# poe-neopixel-controller-v2.net
KiCad netlist of a schematic drawn in EAGLE
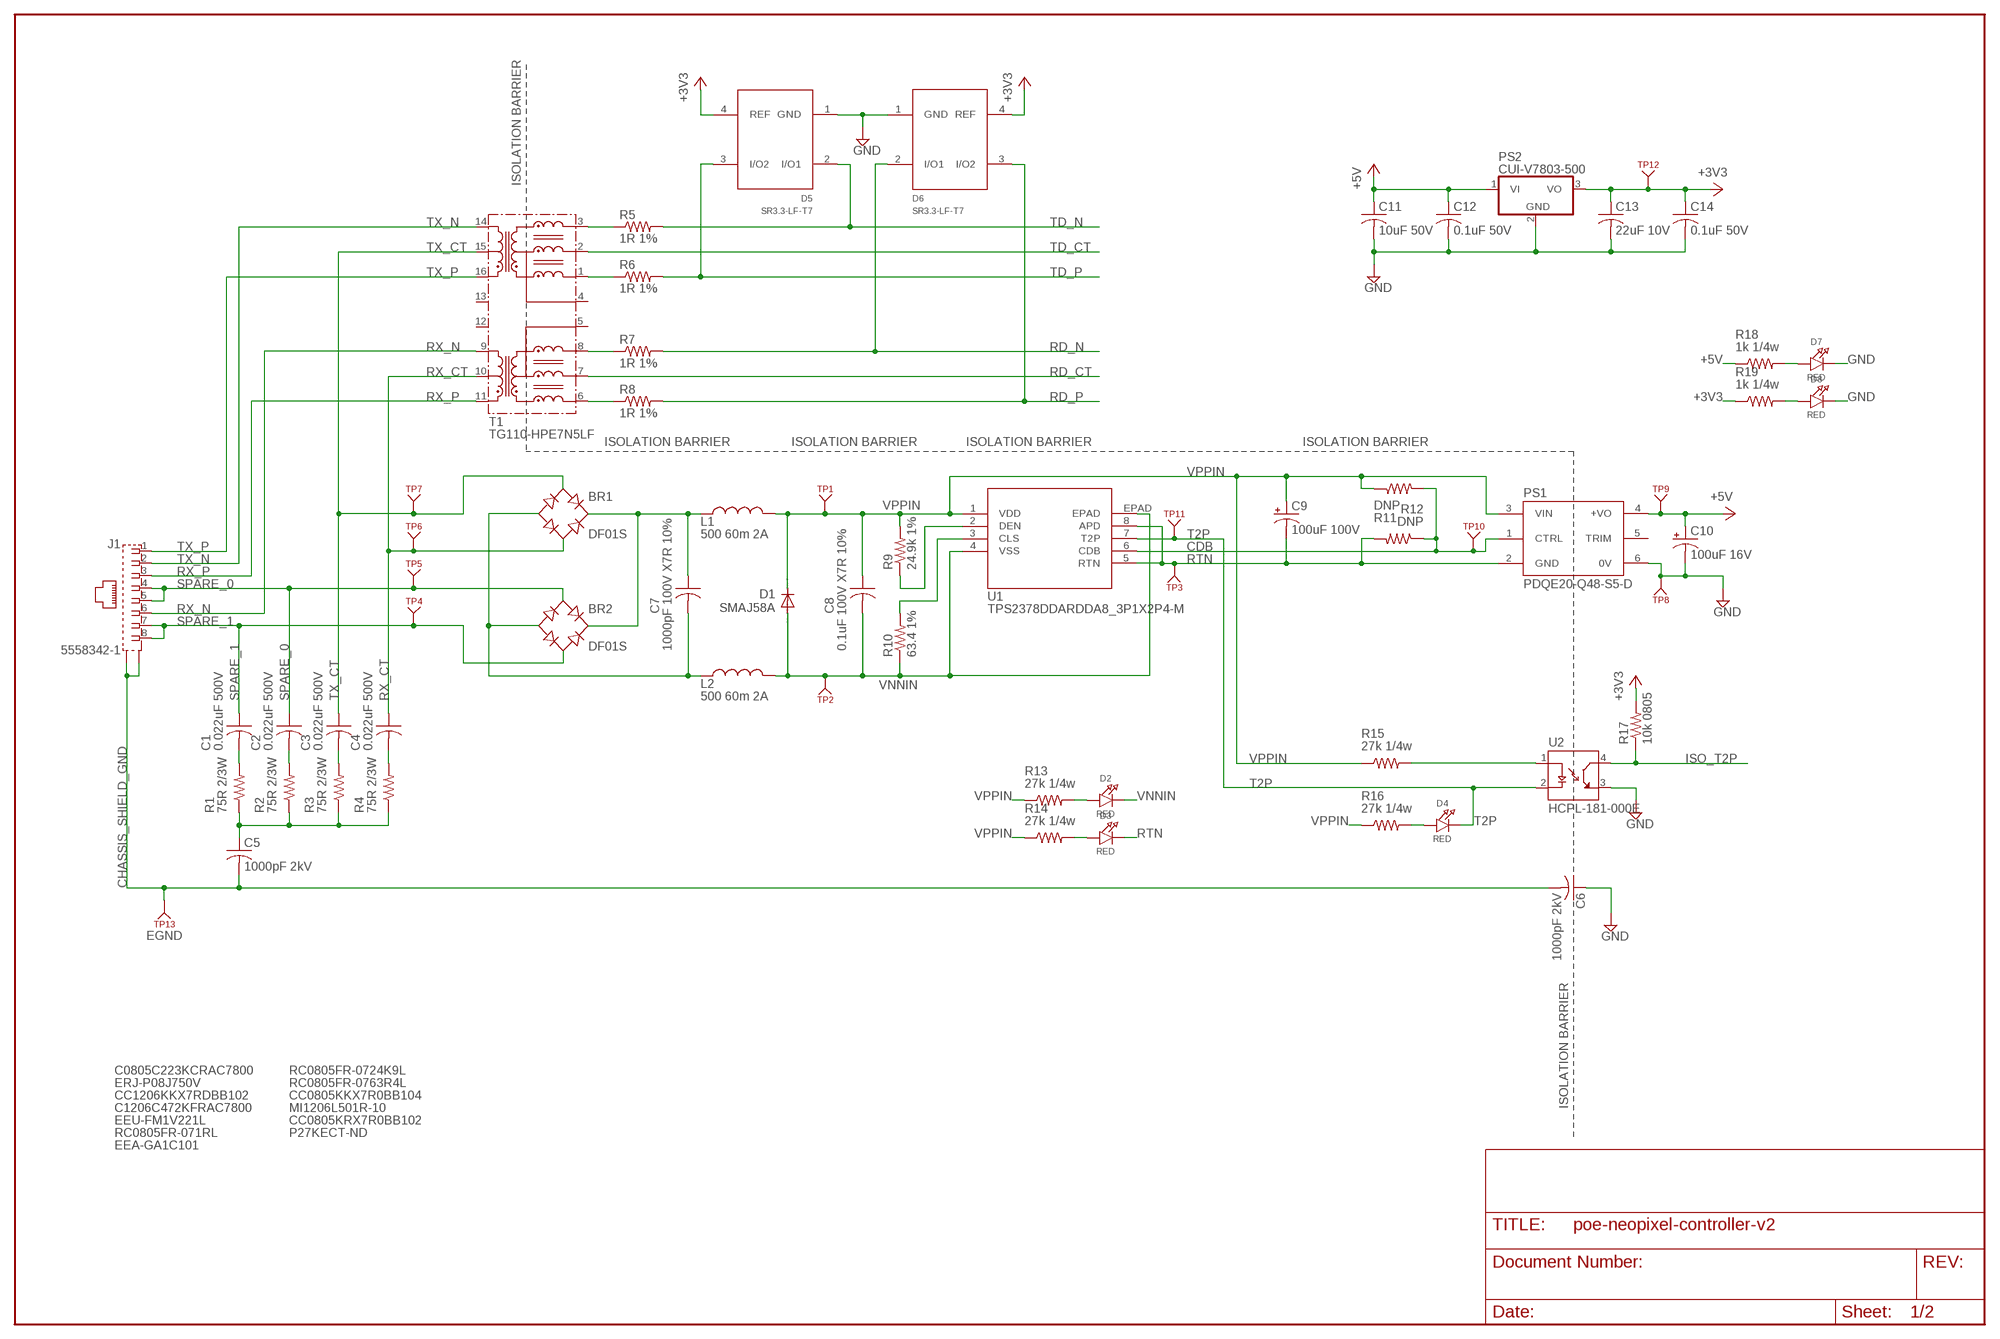
[diagram p0: schematic, sheet 1]
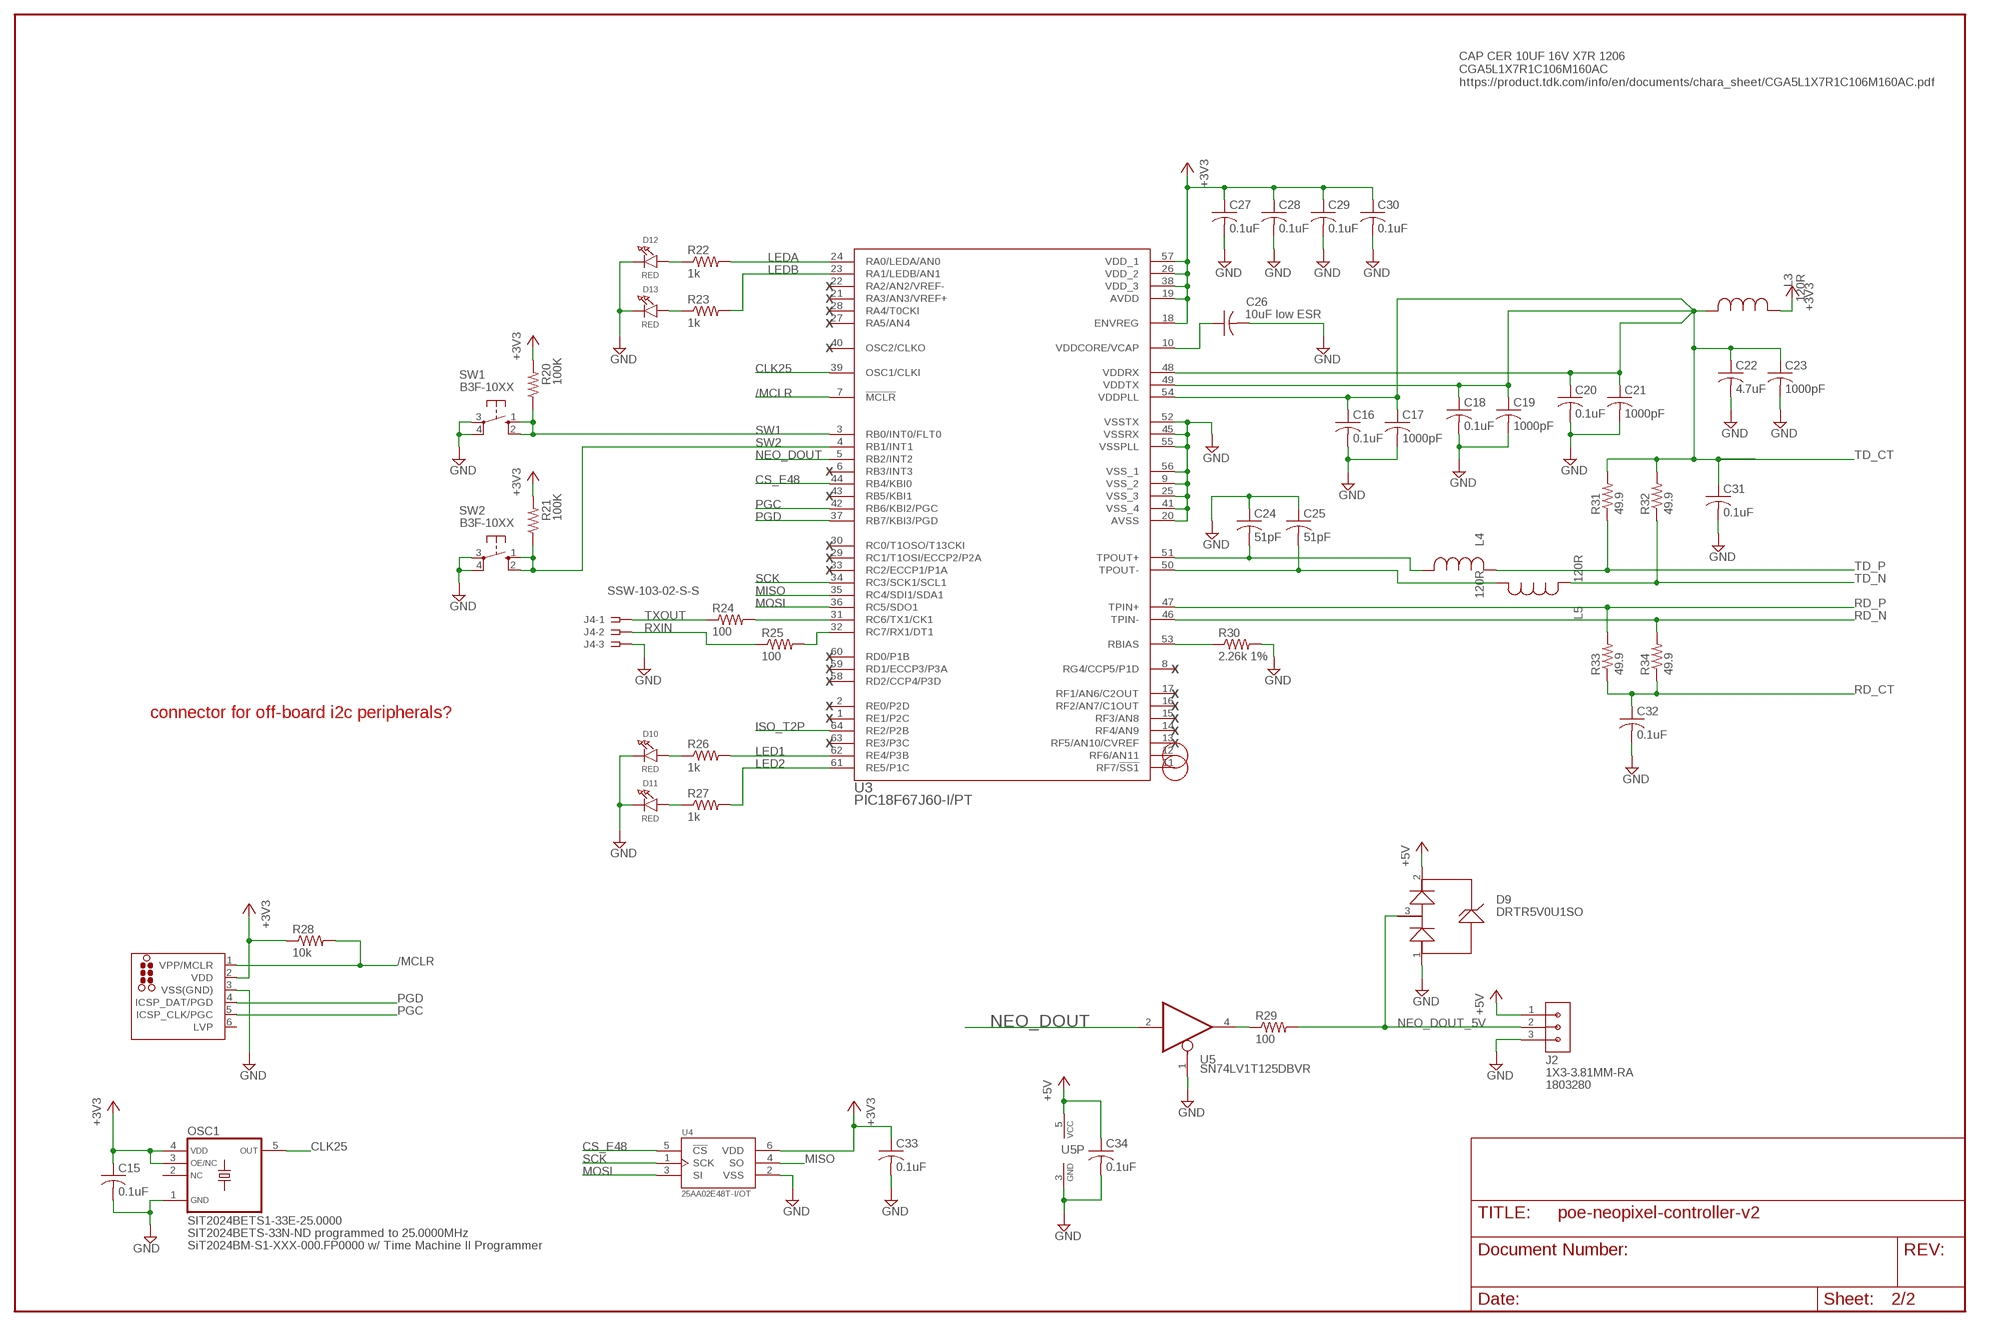
[diagram p1: schematic, sheet 2]

(export (version "E")
  (design (tool "Eeschema 10.0.6"))
  (components
    (comp (ref "C15")
      (value "0.1uF")
      (footprint "eagle-import:C0603")
      (libsource (lib "eagle-import") (part "C-USC0603"))
    )
    (comp (ref "C16")
      (value "0.1uF")
      (footprint "eagle-import:C0805")
      (libsource (lib "eagle-import") (part "C-USC0805"))
    )
    (comp (ref "C17")
      (value "1000pF")
      (footprint "eagle-import:C0805")
      (libsource (lib "eagle-import") (part "C-USC0805"))
    )
    (comp (ref "C18")
      (value "0.1uF")
      (footprint "eagle-import:C0805")
      (libsource (lib "eagle-import") (part "C-USC0805"))
    )
    (comp (ref "C19")
      (value "1000pF")
      (footprint "eagle-import:C0805")
      (libsource (lib "eagle-import") (part "C-USC0805"))
    )
    (comp (ref "C20")
      (value "0.1uF")
      (footprint "eagle-import:C0805")
      (libsource (lib "eagle-import") (part "C-USC0805"))
    )
    (comp (ref "C21")
      (value "1000pF")
      (footprint "eagle-import:C0805")
      (libsource (lib "eagle-import") (part "C-USC0805"))
    )
    (comp (ref "C22")
      (value "4.7uF")
      (footprint "eagle-import:C0805")
      (libsource (lib "eagle-import") (part "C-USC0805"))
    )
    (comp (ref "C23")
      (value "1000pF")
      (footprint "eagle-import:C0805")
      (libsource (lib "eagle-import") (part "C-USC0805"))
    )
    (comp (ref "C24")
      (value "51pF")
      (footprint "eagle-import:C0805")
      (libsource (lib "eagle-import") (part "C-USC0805"))
    )
    (comp (ref "C25")
      (value "51pF")
      (footprint "eagle-import:C0805")
      (libsource (lib "eagle-import") (part "C-USC0805"))
    )
    (comp (ref "C26")
      (value "10uF low ESR")
      (footprint "eagle-import:C1206")
      (libsource (lib "eagle-import") (part "resistor_C-USC1206"))
    )
    (comp (ref "C27")
      (value "0.1uF")
      (footprint "eagle-import:C0603")
      (libsource (lib "eagle-import") (part "C-USC0603"))
    )
    (comp (ref "C28")
      (value "0.1uF")
      (footprint "eagle-import:C0603")
      (libsource (lib "eagle-import") (part "C-USC0603"))
    )
    (comp (ref "C29")
      (value "0.1uF")
      (footprint "eagle-import:C0603")
      (libsource (lib "eagle-import") (part "C-USC0603"))
    )
    (comp (ref "C30")
      (value "0.1uF")
      (footprint "eagle-import:C0603")
      (libsource (lib "eagle-import") (part "C-USC0603"))
    )
    (comp (ref "C31")
      (value "0.1uF")
      (footprint "eagle-import:C0805")
      (libsource (lib "eagle-import") (part "C-USC0805"))
    )
    (comp (ref "C32")
      (value "0.1uF")
      (footprint "eagle-import:C0805")
      (libsource (lib "eagle-import") (part "C-USC0805"))
    )
    (comp (ref "C33")
      (value "0.1uF")
      (footprint "eagle-import:C0603")
      (libsource (lib "eagle-import") (part "C-USC0603"))
    )
    (comp (ref "C34")
      (value "0.1uF")
      (footprint "eagle-import:C0603")
      (libsource (lib "eagle-import") (part "C-USC0603"))
    )
    (comp (ref "D9")
      (value "DRTR5V0U1SO")
      (footprint "eagle-import:SOT23-3")
      (fields (field (name "MFR") "DIODES INC") (field (name "MFR_PART_NO") "DRTR5V0U1SO"))
      (libsource (lib "eagle-import") (part "DRTR5V0U1SO"))
    )
    (comp (ref "D10")
      (value "RED")
      (footprint "eagle-import:CHIPLED_0805_NOOUTLINE")
      (libsource (lib "eagle-import") (part "LED0805_NOOUTLINE"))
    )
    (comp (ref "D11")
      (value "RED")
      (footprint "eagle-import:CHIPLED_0805_NOOUTLINE")
      (libsource (lib "eagle-import") (part "LED0805_NOOUTLINE"))
    )
    (comp (ref "D12")
      (value "RED")
      (footprint "eagle-import:CHIPLED_0805_NOOUTLINE")
      (libsource (lib "eagle-import") (part "LED0805_NOOUTLINE"))
    )
    (comp (ref "D13")
      (value "RED")
      (footprint "eagle-import:CHIPLED_0805_NOOUTLINE")
      (libsource (lib "eagle-import") (part "LED0805_NOOUTLINE"))
    )
    (comp (ref "J2")
      (value "1X3-3.81MM-RA")
      (footprint "eagle-import:CON-PHOENIX-3.81-1X3-RA")
      (fields (field (name "MFR") "PHOENIX") (field (name "MFR_PART_NO") "1803280"))
      (libsource (lib "eagle-import") (part "CON-3.81MM-1X3-PHOENIX-RA"))
    )
    (comp (ref "J3")
      (value "TC2030-MCP-NL")
      (footprint "eagle-import:TC2030-MCP-NL")
      (libsource (lib "eagle-import") (part "TC2030-MCP-NL"))
    )
    (comp (ref "J4")
      (value "SSW-103-02-S-S")
      (footprint "eagle-import:SSW-103-02-S-S")
      (libsource (lib "eagle-import") (part "SSW-103-02-S-S"))
    )
    (comp (ref "L3")
      (value "120R")
      (footprint "eagle-import:IND_1608-M")
      (fields (field (name "MANUFACTURER_PART_NUMBER") "MMZ1608B121CTAH0"))
      (libsource (lib "eagle-import") (part "MMZ1608B121CTAH0IND_1608-M"))
    )
    (comp (ref "L4")
      (value "120R")
      (footprint "eagle-import:IND_1608-M")
      (fields (field (name "MANUFACTURER_PART_NUMBER") "MMZ1608B121CTAH0"))
      (libsource (lib "eagle-import") (part "MMZ1608B121CTAH0IND_1608-M"))
    )
    (comp (ref "L5")
      (value "120R")
      (footprint "eagle-import:IND_1608-M")
      (fields (field (name "MANUFACTURER_PART_NUMBER") "MMZ1608B121CTAH0"))
      (libsource (lib "eagle-import") (part "MMZ1608B121CTAH0IND_1608-M"))
    )
    (comp (ref "OSC1")
      (value "SIT2024BETS1-33E-25.0000")
      (footprint "eagle-import:SOT23-5")
      (libsource (lib "eagle-import") (part "SIT2024BETS1-33E-10.0000"))
    )
    (comp (ref "R20")
      (value "100K")
      (footprint "eagle-import:R0805")
      (libsource (lib "eagle-import") (part "R-US_R0805"))
    )
    (comp (ref "R21")
      (value "100K")
      (footprint "eagle-import:R0805")
      (libsource (lib "eagle-import") (part "R-US_R0805"))
    )
    (comp (ref "R22")
      (value "1k")
      (footprint "eagle-import:R0805")
      (libsource (lib "eagle-import") (part "R-US_R0805"))
    )
    (comp (ref "R23")
      (value "1k")
      (footprint "eagle-import:R0805")
      (libsource (lib "eagle-import") (part "R-US_R0805"))
    )
    (comp (ref "R24")
      (value "100")
      (footprint "eagle-import:R0805")
      (libsource (lib "eagle-import") (part "R-US_R0805"))
    )
    (comp (ref "R25")
      (value "100")
      (footprint "eagle-import:R0805")
      (libsource (lib "eagle-import") (part "R-US_R0805"))
    )
    (comp (ref "R26")
      (value "1k")
      (footprint "eagle-import:R0805")
      (libsource (lib "eagle-import") (part "R-US_R0805"))
    )
    (comp (ref "R27")
      (value "1k")
      (footprint "eagle-import:R0805")
      (libsource (lib "eagle-import") (part "R-US_R0805"))
    )
    (comp (ref "R28")
      (value "10k")
      (footprint "eagle-import:R0805")
      (libsource (lib "eagle-import") (part "R-US_R0805"))
    )
    (comp (ref "R29")
      (value "100")
      (footprint "eagle-import:R0805")
      (libsource (lib "eagle-import") (part "R-US_R0805"))
    )
    (comp (ref "R30")
      (value "2.26k 1%")
      (footprint "eagle-import:R0805")
      (libsource (lib "eagle-import") (part "R-US_R0805"))
    )
    (comp (ref "R31")
      (value "49.9")
      (footprint "eagle-import:R0805")
      (libsource (lib "eagle-import") (part "R-US_R0805"))
    )
    (comp (ref "R32")
      (value "49.9")
      (footprint "eagle-import:R0805")
      (libsource (lib "eagle-import") (part "R-US_R0805"))
    )
    (comp (ref "R33")
      (value "49.9")
      (footprint "eagle-import:R0805")
      (libsource (lib "eagle-import") (part "R-US_R0805"))
    )
    (comp (ref "R34")
      (value "49.9")
      (footprint "eagle-import:R0805")
      (libsource (lib "eagle-import") (part "R-US_R0805"))
    )
    (comp (ref "SW1")
      (value "B3F-10XX")
      (footprint "eagle-import:B3F-10XX")
      (libsource (lib "eagle-import") (part "10-XX"))
    )
    (comp (ref "SW2")
      (value "B3F-10XX")
      (footprint "eagle-import:B3F-10XX")
      (libsource (lib "eagle-import") (part "10-XX"))
    )
    (comp (ref "U3")
      (value "PIC18F67J60-I/PT")
      (footprint "eagle-import:TQFP64_10X10MC")
      (fields (field (name "MANUFACTURER_PART_NUMBER") "PIC18F67J60IPT"))
      (libsource (lib "eagle-import") (part "PIC18F67J60-I/PT"))
    )
    (comp (ref "U4")
      (value "25AA02E48T-I/OT")
      (footprint "eagle-import:SOT95P270X145-6N")
      (fields (field (name "DIGI-KEY_PART_NUMBER") "25AA02E48T-I/OTCT-ND") (field (name "MF") "Microchip"))
      (libsource (lib "eagle-import") (part "25AA02E48T-I/OT"))
    )
    (comp (ref "U5")
      (value "SN74LV1T125DBVR")
      (footprint "eagle-import:SOT23-5")
      (fields (field (name "MFR") "TI") (field (name "MFR_PART_NO") "SN74LV1T125DBVR"))
      (libsource (lib "eagle-import") (part "741G125DBVAHC"))
    )
    (comp (ref "BR1")
      (value "DF01S")
      (footprint "eagle-import:DFS")
      (libsource (lib "eagle-import") (part "DFS01"))
    )
    (comp (ref "BR2")
      (value "DF01S")
      (footprint "eagle-import:DFS")
      (libsource (lib "eagle-import") (part "DFS01"))
    )
    (comp (ref "C1")
      (value "0.022uF 500V")
      (footprint "eagle-import:C1206")
      (libsource (lib "eagle-import") (part "C-USC1206"))
    )
    (comp (ref "C2")
      (value "0.022uF 500V")
      (footprint "eagle-import:C1206")
      (libsource (lib "eagle-import") (part "C-USC1206"))
    )
    (comp (ref "C3")
      (value "0.022uF 500V")
      (footprint "eagle-import:C1206")
      (libsource (lib "eagle-import") (part "C-USC1206"))
    )
    (comp (ref "C4")
      (value "0.022uF 500V")
      (footprint "eagle-import:C1206")
      (libsource (lib "eagle-import") (part "C-USC1206"))
    )
    (comp (ref "C5")
      (value "1000pF 2kV")
      (footprint "eagle-import:C1206K")
      (libsource (lib "eagle-import") (part "C-USC1206K"))
    )
    (comp (ref "C6")
      (value "1000pF 2kV")
      (footprint "eagle-import:C1206K")
      (libsource (lib "eagle-import") (part "C-USC1206K"))
    )
    (comp (ref "C7")
      (value "1000pF 100V X7R 10%")
      (footprint "eagle-import:C0805")
      (libsource (lib "eagle-import") (part "C-USC0805"))
    )
    (comp (ref "C8")
      (value "0.1uF 100V X7R 10%")
      (footprint "eagle-import:C0805")
      (libsource (lib "eagle-import") (part "C-USC0805"))
    )
    (comp (ref "C9")
      (value "100uF 100V")
      (footprint "eagle-import:E5-10,5")
      (libsource (lib "eagle-import") (part "CPOL-USE5-10.5"))
    )
    (comp (ref "C10")
      (value "100uF 16V")
      (footprint "eagle-import:E2,5-7")
      (libsource (lib "eagle-import") (part "CPOL-USE2.5-7"))
    )
    (comp (ref "C11")
      (value "10uF 50V")
      (footprint "eagle-import:C1210K")
      (fields (field (name "MFR") "KEMET") (field (name "MFR_PART_NO") "C1210C106K5RACTU"))
      (libsource (lib "eagle-import") (part "C-USC1210K"))
    )
    (comp (ref "C12")
      (value "0.1uF 50V")
      (footprint "eagle-import:C0805")
      (fields (field (name "MFR") "KEMET") (field (name "MFR_PART_NO") "C1206S104M5RACTU"))
      (libsource (lib "eagle-import") (part "C-USC0805"))
    )
    (comp (ref "C13")
      (value "22uF 10V")
      (footprint "eagle-import:C1206K")
      (fields (field (name "MFR") "KEMET") (field (name "MFR_PART_NO") "C1206C226K8RAC7800"))
      (libsource (lib "eagle-import") (part "C-USC1206K"))
    )
    (comp (ref "C14")
      (value "0.1uF 50V")
      (footprint "eagle-import:C0805")
      (fields (field (name "MFR") "KEMET") (field (name "MFR_PART_NO") "C1206S104M5RACTU"))
      (libsource (lib "eagle-import") (part "C-USC0805"))
    )
    (comp (ref "D1")
      (value "SMAJ58A")
      (footprint "eagle-import:DO214AC")
      (libsource (lib "eagle-import") (part "DIODE-DO214AC"))
    )
    (comp (ref "D2")
      (value "RED")
      (footprint "eagle-import:CHIPLED_0805_NOOUTLINE")
      (libsource (lib "eagle-import") (part "LED0805_NOOUTLINE"))
    )
    (comp (ref "D3")
      (value "RED")
      (footprint "eagle-import:CHIPLED_0805_NOOUTLINE")
      (libsource (lib "eagle-import") (part "LED0805_NOOUTLINE"))
    )
    (comp (ref "D4")
      (value "RED")
      (footprint "eagle-import:CHIPLED_0805_NOOUTLINE")
      (libsource (lib "eagle-import") (part "LED0805_NOOUTLINE"))
    )
    (comp (ref "D5")
      (value "SR3.3-LF-T7")
      (footprint "eagle-import:SOT143B")
      (libsource (lib "eagle-import") (part "SR3.3-LF-T7"))
    )
    (comp (ref "D6")
      (value "SR3.3-LF-T7")
      (footprint "eagle-import:SOT143B")
      (libsource (lib "eagle-import") (part "SR3.3-LF-T7"))
    )
    (comp (ref "D7")
      (value "RED")
      (footprint "eagle-import:CHIPLED_0805_NOOUTLINE")
      (libsource (lib "eagle-import") (part "LED0805_NOOUTLINE"))
    )
    (comp (ref "D8")
      (value "RED")
      (footprint "eagle-import:CHIPLED_0805_NOOUTLINE")
      (libsource (lib "eagle-import") (part "LED0805_NOOUTLINE"))
    )
    (comp (ref "J1")
      (value "5558342-1")
      (footprint "eagle-import:TE_5558342-1")
      (fields (field (name "DIGI-KEY_PART_NUMBER") "A31466-ND") (field (name "MF") "TE Connectivity"))
      (libsource (lib "eagle-import") (part "5558342-1"))
    )
    (comp (ref "L1")
      (value "500 60m 2A")
      (footprint "eagle-import:L3216C")
      (libsource (lib "eagle-import") (part "L-USL3216C"))
    )
    (comp (ref "L2")
      (value "500 60m 2A")
      (footprint "eagle-import:L3216C")
      (libsource (lib "eagle-import") (part "L-USL3216C"))
    )
    (comp (ref "PS1")
      (value "PDQE20-Q48-S5-D")
      (footprint "eagle-import:CONV_PDQE20-Q48-S5-D")
      (fields (field (name "DIGI-KEY_PART_NUMBER") "102-6272-ND") (field (name "MF") "CUI Inc."))
      (libsource (lib "eagle-import") (part "PDQE20-Q48-S5-D"))
    )
    (comp (ref "PS2")
      (value "CUI-V7803-500")
      (footprint "eagle-import:CUI-78XX-500")
      (libsource (lib "eagle-import") (part "CUI-V7803-500"))
    )
    (comp (ref "R1")
      (value "75R 2/3W")
      (footprint "eagle-import:R1206")
      (libsource (lib "eagle-import") (part "R-US_R1206"))
    )
    (comp (ref "R2")
      (value "75R 2/3W")
      (footprint "eagle-import:R1206")
      (libsource (lib "eagle-import") (part "R-US_R1206"))
    )
    (comp (ref "R3")
      (value "75R 2/3W")
      (footprint "eagle-import:R1206")
      (libsource (lib "eagle-import") (part "R-US_R1206"))
    )
    (comp (ref "R4")
      (value "75R 2/3W")
      (footprint "eagle-import:R1206")
      (libsource (lib "eagle-import") (part "R-US_R1206"))
    )
    (comp (ref "R5")
      (value "1R 1%")
      (footprint "eagle-import:R0805")
      (libsource (lib "eagle-import") (part "R-US_R0805"))
    )
    (comp (ref "R6")
      (value "1R 1%")
      (footprint "eagle-import:R0805")
      (libsource (lib "eagle-import") (part "R-US_R0805"))
    )
    (comp (ref "R7")
      (value "1R 1%")
      (footprint "eagle-import:R0805")
      (libsource (lib "eagle-import") (part "R-US_R0805"))
    )
    (comp (ref "R8")
      (value "1R 1%")
      (footprint "eagle-import:R0805")
      (libsource (lib "eagle-import") (part "R-US_R0805"))
    )
    (comp (ref "R9")
      (value "24.9k 1%")
      (footprint "eagle-import:R0805")
      (libsource (lib "eagle-import") (part "R-US_R0805"))
    )
    (comp (ref "R10")
      (value "63.4 1%")
      (footprint "eagle-import:R0805")
      (libsource (lib "eagle-import") (part "R-US_R0805"))
    )
    (comp (ref "R11")
      (value "DNP")
      (footprint "eagle-import:R1206")
      (libsource (lib "eagle-import") (part "R-US_R1206"))
    )
    (comp (ref "R12")
      (value "DNP")
      (footprint "eagle-import:R1206")
      (libsource (lib "eagle-import") (part "R-US_R1206"))
    )
    (comp (ref "R13")
      (value "27k 1/4w")
      (footprint "eagle-import:R1206")
      (libsource (lib "eagle-import") (part "R-US_R1206"))
    )
    (comp (ref "R14")
      (value "27k 1/4w")
      (footprint "eagle-import:R1206")
      (libsource (lib "eagle-import") (part "R-US_R1206"))
    )
    (comp (ref "R15")
      (value "27k 1/4w")
      (footprint "eagle-import:R1206")
      (libsource (lib "eagle-import") (part "R-US_R1206"))
    )
    (comp (ref "R16")
      (value "27k 1/4w")
      (footprint "eagle-import:R1206")
      (libsource (lib "eagle-import") (part "R-US_R1206"))
    )
    (comp (ref "R17")
      (value "10k 0805")
      (footprint "eagle-import:R0805")
      (libsource (lib "eagle-import") (part "resistor_R-US_R0805"))
    )
    (comp (ref "R18")
      (value "1k 1/4w")
      (footprint "eagle-import:R0805")
      (libsource (lib "eagle-import") (part "R-US_R0805"))
    )
    (comp (ref "R19")
      (value "1k 1/4w")
      (footprint "eagle-import:R0805")
      (libsource (lib "eagle-import") (part "R-US_R0805"))
    )
    (comp (ref "T1")
      (value "TG110-HPE7N5LF")
      (footprint "eagle-import:RP-ULTRA")
      (libsource (lib "eagle-import") (part "TG110-HPE7N5LF"))
    )
    (comp (ref "TP1")
      (value "KEYSTONE_500X")
      (footprint "eagle-import:KEYSTONE_TP500X")
      (libsource (lib "eagle-import") (part "KEYSTONE_500X"))
    )
    (comp (ref "TP2")
      (value "KEYSTONE_500X")
      (footprint "eagle-import:KEYSTONE_TP500X")
      (libsource (lib "eagle-import") (part "KEYSTONE_500X"))
    )
    (comp (ref "TP3")
      (value "KEYSTONE_500X")
      (footprint "eagle-import:KEYSTONE_TP500X")
      (libsource (lib "eagle-import") (part "KEYSTONE_500X"))
    )
    (comp (ref "TP4")
      (value "KEYSTONE_500X")
      (footprint "eagle-import:KEYSTONE_TP500X")
      (libsource (lib "eagle-import") (part "KEYSTONE_500X"))
    )
    (comp (ref "TP5")
      (value "KEYSTONE_500X")
      (footprint "eagle-import:KEYSTONE_TP500X")
      (libsource (lib "eagle-import") (part "KEYSTONE_500X"))
    )
    (comp (ref "TP6")
      (value "KEYSTONE_500X")
      (footprint "eagle-import:KEYSTONE_TP500X")
      (libsource (lib "eagle-import") (part "KEYSTONE_500X"))
    )
    (comp (ref "TP7")
      (value "KEYSTONE_500X")
      (footprint "eagle-import:KEYSTONE_TP500X")
      (libsource (lib "eagle-import") (part "KEYSTONE_500X"))
    )
    (comp (ref "TP8")
      (value "KEYSTONE_500X")
      (footprint "eagle-import:KEYSTONE_TP500X")
      (libsource (lib "eagle-import") (part "KEYSTONE_500X"))
    )
    (comp (ref "TP9")
      (value "KEYSTONE_500X")
      (footprint "eagle-import:KEYSTONE_TP500X")
      (libsource (lib "eagle-import") (part "KEYSTONE_500X"))
    )
    (comp (ref "TP10")
      (value "KEYSTONE_500X")
      (footprint "eagle-import:KEYSTONE_TP500X")
      (libsource (lib "eagle-import") (part "KEYSTONE_500X"))
    )
    (comp (ref "TP11")
      (value "KEYSTONE_500X")
      (footprint "eagle-import:KEYSTONE_TP500X")
      (libsource (lib "eagle-import") (part "KEYSTONE_500X"))
    )
    (comp (ref "TP12")
      (value "KEYSTONE_500X")
      (footprint "eagle-import:KEYSTONE_TP500X")
      (libsource (lib "eagle-import") (part "KEYSTONE_500X"))
    )
    (comp (ref "TP13")
      (value "KEYSTONE_500X")
      (footprint "eagle-import:KEYSTONE_TP500X")
      (libsource (lib "eagle-import") (part "KEYSTONE_500X"))
    )
    (comp (ref "U1")
      (value "TPS2378DDARDDA8_3P1X2P4-M")
      (footprint "eagle-import:DDA8_3P1X2P4-M")
      (fields (field (name "MANUFACTURER_PART_NUMBER") "TPS2378DDAR"))
      (libsource (lib "eagle-import") (part "TPS2378DDARDDA8_3P1X2P4-M"))
    )
    (comp (ref "U2")
      (value "HCPL-181-000E")
      (footprint "eagle-import:SOIC254P675X240-4N")
      (fields (field (name "DIGI-KEY_PART_NUMBER") "516-1646-1-ND") (field (name "MF") "Broadcom Limited"))
      (libsource (lib "eagle-import") (part "HCPL-181-000E"))
    )
  )
  (nets
    (net (code "1") (name "+3V3") (class "Default")
      (node (ref "C13") (pin "1") (pinfunction "1_1") (pintype "passive"))
      (node (ref "C14") (pin "1") (pinfunction "1_1") (pintype "passive"))
      (node (ref "C15") (pin "1") (pinfunction "1_1") (pintype "passive"))
      (node (ref "C27") (pin "1") (pinfunction "1_1") (pintype "passive"))
      (node (ref "C28") (pin "1") (pinfunction "1_1") (pintype "passive"))
      (node (ref "C29") (pin "1") (pinfunction "1_1") (pintype "passive"))
      (node (ref "C30") (pin "1") (pinfunction "1_1") (pintype "passive"))
      (node (ref "C33") (pin "1") (pinfunction "1_1") (pintype "passive"))
      (node (ref "D5") (pin "4") (pinfunction "REF_4") (pintype "bidirectional"))
      (node (ref "D6") (pin "4") (pinfunction "REF_4") (pintype "bidirectional"))
      (node (ref "J3") (pin "2") (pinfunction "VDD_2") (pintype "power_in"))
      (node (ref "L3") (pin "2") (pinfunction "2_2") (pintype "passive"))
      (node (ref "OSC1") (pin "3") (pinfunction "OE/NC_3") (pintype "bidirectional"))
      (node (ref "OSC1") (pin "4") (pinfunction "VDD_4") (pintype "bidirectional"))
      (node (ref "PS2") (pin "3") (pinfunction "VO_3") (pintype "passive"))
      (node (ref "R17") (pin "2") (pinfunction "2_2") (pintype "passive"))
      (node (ref "R19") (pin "1") (pinfunction "1_1") (pintype "passive"))
      (node (ref "R20") (pin "2") (pinfunction "2_2") (pintype "passive"))
      (node (ref "R21") (pin "2") (pinfunction "2_2") (pintype "passive"))
      (node (ref "R28") (pin "1") (pinfunction "1_1") (pintype "passive"))
      (node (ref "TP12") (pin "1") (pinfunction "P$1_1") (pintype "bidirectional"))
      (node (ref "U3") (pin "18") (pinfunction "ENVREG_18") (pintype "passive"))
      (node (ref "U3") (pin "19") (pinfunction "AVDD_19") (pintype "passive"))
      (node (ref "U3") (pin "26") (pinfunction "VDD_2_26") (pintype "passive"))
      (node (ref "U3") (pin "38") (pinfunction "VDD_3_38") (pintype "passive"))
      (node (ref "U3") (pin "57") (pinfunction "VDD_1_57") (pintype "passive"))
      (node (ref "U4") (pin "6") (pinfunction "VDD_6") (pintype "power_in"))
    )
    (net (code "2") (name "+5V") (class "Default")
      (node (ref "C10") (pin "+") (pinfunction "+_+") (pintype "passive"))
      (node (ref "C11") (pin "1") (pinfunction "1_1") (pintype "passive"))
      (node (ref "C12") (pin "1") (pinfunction "1_1") (pintype "passive"))
      (node (ref "C34") (pin "1") (pinfunction "1_1") (pintype "passive"))
      (node (ref "D9") (pin "2") (pinfunction "2_2") (pintype "bidirectional"))
      (node (ref "J2") (pin "1") (pinfunction "1_1") (pintype "bidirectional"))
      (node (ref "PS1") (pin "4") (pinfunction "+VO_4") (pintype "output"))
      (node (ref "PS2") (pin "1") (pinfunction "VI_1") (pintype "input"))
      (node (ref "R18") (pin "1") (pinfunction "1_1") (pintype "passive"))
      (node (ref "TP9") (pin "1") (pinfunction "P$1_1") (pintype "bidirectional"))
      (node (ref "U5") (pin "5") (pinfunction "VCC_5") (pintype "power_in"))
    )
    (net (code "3") (name "CDB") (class "Default")
      (node (ref "PS1") (pin "1") (pinfunction "CTRL_1") (pintype "input"))
      (node (ref "R11") (pin "2") (pinfunction "2_2") (pintype "passive"))
      (node (ref "R12") (pin "1") (pinfunction "1_1") (pintype "passive"))
      (node (ref "TP10") (pin "1") (pinfunction "P$1_1") (pintype "bidirectional"))
      (node (ref "U1") (pin "6") (pinfunction "CDB_6") (pintype "output"))
    )
    (net (code "4") (name "CHASSIS_SHIELD_GND") (class "Default")
      (node (ref "C5") (pin "2") (pinfunction "2_2") (pintype "passive"))
      (node (ref "C6") (pin "2") (pinfunction "2_2") (pintype "passive"))
      (node (ref "J1") (pin "SH1") (pinfunction "S1_SH1") (pintype "passive"))
      (node (ref "J1") (pin "SH2") (pinfunction "S2_SH2") (pintype "passive"))
      (node (ref "TP13") (pin "1") (pinfunction "P$1_1") (pintype "bidirectional"))
    )
    (net (code "5") (name "CLK25") (class "Default")
      (node (ref "OSC1") (pin "5") (pinfunction "OUT_5") (pintype "bidirectional"))
      (node (ref "U3") (pin "39") (pinfunction "OSC1/CLKI_39") (pintype "passive"))
    )
    (net (code "6") (name "CS_E48") (class "Default")
      (node (ref "U3") (pin "44") (pinfunction "RB4/KBI0_44") (pintype "passive"))
      (node (ref "U4") (pin "5") (pinfunction "~{CS}_5") (pintype "input"))
    )
    (net (code "7") (name "GND") (class "Default")
      (node (ref "C10") (pin "-") (pinfunction "-_-") (pintype "passive"))
      (node (ref "C11") (pin "2") (pinfunction "2_2") (pintype "passive"))
      (node (ref "C12") (pin "2") (pinfunction "2_2") (pintype "passive"))
      (node (ref "C13") (pin "2") (pinfunction "2_2") (pintype "passive"))
      (node (ref "C14") (pin "2") (pinfunction "2_2") (pintype "passive"))
      (node (ref "C15") (pin "2") (pinfunction "2_2") (pintype "passive"))
      (node (ref "C16") (pin "2") (pinfunction "2_2") (pintype "passive"))
      (node (ref "C17") (pin "2") (pinfunction "2_2") (pintype "passive"))
      (node (ref "C18") (pin "2") (pinfunction "2_2") (pintype "passive"))
      (node (ref "C19") (pin "2") (pinfunction "2_2") (pintype "passive"))
      (node (ref "C20") (pin "2") (pinfunction "2_2") (pintype "passive"))
      (node (ref "C21") (pin "2") (pinfunction "2_2") (pintype "passive"))
      (node (ref "C22") (pin "2") (pinfunction "2_2") (pintype "passive"))
      (node (ref "C23") (pin "2") (pinfunction "2_2") (pintype "passive"))
      (node (ref "C24") (pin "1") (pinfunction "1_1") (pintype "passive"))
      (node (ref "C25") (pin "1") (pinfunction "1_1") (pintype "passive"))
      (node (ref "C26") (pin "2") (pinfunction "2_2") (pintype "passive"))
      (node (ref "C27") (pin "2") (pinfunction "2_2") (pintype "passive"))
      (node (ref "C28") (pin "2") (pinfunction "2_2") (pintype "passive"))
      (node (ref "C29") (pin "2") (pinfunction "2_2") (pintype "passive"))
      (node (ref "C30") (pin "2") (pinfunction "2_2") (pintype "passive"))
      (node (ref "C31") (pin "2") (pinfunction "2_2") (pintype "passive"))
      (node (ref "C32") (pin "2") (pinfunction "2_2") (pintype "passive"))
      (node (ref "C33") (pin "2") (pinfunction "2_2") (pintype "passive"))
      (node (ref "C34") (pin "2") (pinfunction "2_2") (pintype "passive"))
      (node (ref "C6") (pin "1") (pinfunction "1_1") (pintype "passive"))
      (node (ref "D10") (pin "C") (pinfunction "C_C") (pintype "passive"))
      (node (ref "D11") (pin "C") (pinfunction "C_C") (pintype "passive"))
      (node (ref "D12") (pin "C") (pinfunction "C_C") (pintype "passive"))
      (node (ref "D13") (pin "C") (pinfunction "C_C") (pintype "passive"))
      (node (ref "D5") (pin "1") (pinfunction "GND_1") (pintype "bidirectional"))
      (node (ref "D6") (pin "1") (pinfunction "GND_1") (pintype "bidirectional"))
      (node (ref "D7") (pin "C") (pinfunction "C_C") (pintype "passive"))
      (node (ref "D8") (pin "C") (pinfunction "C_C") (pintype "passive"))
      (node (ref "D9") (pin "1") (pinfunction "3_1") (pintype "bidirectional"))
      (node (ref "J2") (pin "3") (pinfunction "3_3") (pintype "bidirectional"))
      (node (ref "J3") (pin "3") (pinfunction "VSS(GND)_3") (pintype "power_in"))
      (node (ref "J4") (pin "3") (pinfunction "1_3") (pintype "passive"))
      (node (ref "OSC1") (pin "1") (pinfunction "GND_1") (pintype "bidirectional"))
      (node (ref "PS1") (pin "6") (pinfunction "0V_6") (pintype "output"))
      (node (ref "PS2") (pin "2") (pinfunction "GND_2") (pintype "passive"))
      (node (ref "R30") (pin "2") (pinfunction "2_2") (pintype "passive"))
      (node (ref "SW1") (pin "3") (pinfunction "P_3") (pintype "passive"))
      (node (ref "SW1") (pin "4") (pinfunction "P1_4") (pintype "passive"))
      (node (ref "SW2") (pin "3") (pinfunction "P_3") (pintype "passive"))
      (node (ref "SW2") (pin "4") (pinfunction "P1_4") (pintype "passive"))
      (node (ref "TP8") (pin "1") (pinfunction "P$1_1") (pintype "bidirectional"))
      (node (ref "U2") (pin "3") (pinfunction "EMITTER_3") (pintype "passive"))
      (node (ref "U3") (pin "20") (pinfunction "AVSS_20") (pintype "passive"))
      (node (ref "U3") (pin "25") (pinfunction "VSS_3_25") (pintype "passive"))
      (node (ref "U3") (pin "41") (pinfunction "VSS_4_41") (pintype "passive"))
      (node (ref "U3") (pin "45") (pinfunction "VSSRX_45") (pintype "passive"))
      (node (ref "U3") (pin "52") (pinfunction "VSSTX_52") (pintype "passive"))
      (node (ref "U3") (pin "55") (pinfunction "VSSPLL_55") (pintype "passive"))
      (node (ref "U3") (pin "56") (pinfunction "VSS_1_56") (pintype "passive"))
      (node (ref "U3") (pin "9") (pinfunction "VSS_2_9") (pintype "passive"))
      (node (ref "U4") (pin "2") (pinfunction "VSS_2") (pintype "power_in"))
      (node (ref "U5") (pin "1") (pinfunction "OE_1") (pintype "input"))
      (node (ref "U5") (pin "3") (pinfunction "GND_3") (pintype "power_in"))
    )
    (net (code "8") (name "ISO_T2P") (class "Default")
      (node (ref "R17") (pin "1") (pinfunction "1_1") (pintype "passive"))
      (node (ref "U2") (pin "4") (pinfunction "COLLECTOR_4") (pintype "passive"))
      (node (ref "U3") (pin "64") (pinfunction "RE2/P2B_64") (pintype "passive"))
    )
    (net (code "9") (name "LED1") (class "Default")
      (node (ref "R26") (pin "2") (pinfunction "2_2") (pintype "passive"))
      (node (ref "U3") (pin "62") (pinfunction "RE4/P3B_62") (pintype "passive"))
    )
    (net (code "10") (name "LED2") (class "Default")
      (node (ref "R27") (pin "2") (pinfunction "2_2") (pintype "passive"))
      (node (ref "U3") (pin "61") (pinfunction "RE5/P1C_61") (pintype "passive"))
    )
    (net (code "11") (name "LEDA") (class "Default")
      (node (ref "R22") (pin "2") (pinfunction "2_2") (pintype "passive"))
      (node (ref "U3") (pin "24") (pinfunction "RA0/LEDA/AN0_24") (pintype "passive"))
    )
    (net (code "12") (name "LEDB") (class "Default")
      (node (ref "R23") (pin "2") (pinfunction "2_2") (pintype "passive"))
      (node (ref "U3") (pin "23") (pinfunction "RA1/LEDB/AN1_23") (pintype "passive"))
    )
    (net (code "13") (name "MISO") (class "Default")
      (node (ref "U3") (pin "35") (pinfunction "RC4/SDI1/SDA1_35") (pintype "passive"))
      (node (ref "U4") (pin "4") (pinfunction "SO_4") (pintype "output"))
    )
    (net (code "14") (name "MOSI") (class "Default")
      (node (ref "U3") (pin "36") (pinfunction "RC5/SDO1_36") (pintype "passive"))
      (node (ref "U4") (pin "3") (pinfunction "SI_3") (pintype "input"))
    )
    (net (code "15") (name "NEO_DOUT") (class "Default")
      (node (ref "U3") (pin "5") (pinfunction "RB2/INT2_5") (pintype "passive"))
      (node (ref "U5") (pin "2") (pinfunction "I_2") (pintype "input"))
    )
    (net (code "16") (name "NEO_DOUT_5V") (class "Default")
      (node (ref "D9") (pin "3") (pinfunction "1_3") (pintype "bidirectional"))
      (node (ref "J2") (pin "2") (pinfunction "2_2") (pintype "bidirectional"))
      (node (ref "R29") (pin "2") (pinfunction "2_2") (pintype "passive"))
    )
    (net (code "17") (name "Net-(BR1-Pad+)") (class "Default")
      (node (ref "BR1") (pin "+") (pinfunction "+_+") (pintype "passive"))
      (node (ref "BR2") (pin "+") (pinfunction "+_+") (pintype "passive"))
      (node (ref "C7") (pin "1") (pinfunction "1_1") (pintype "passive"))
      (node (ref "L1") (pin "1") (pinfunction "1_1") (pintype "passive"))
    )
    (net (code "18") (name "Net-(BR1-Pad-)") (class "Default")
      (node (ref "BR1") (pin "-") (pinfunction "-_-") (pintype "passive"))
      (node (ref "BR2") (pin "-") (pinfunction "-_-") (pintype "passive"))
      (node (ref "C7") (pin "2") (pinfunction "2_2") (pintype "passive"))
      (node (ref "L2") (pin "1") (pinfunction "1_1") (pintype "passive"))
    )
    (net (code "19") (name "Net-(C1-Pad2)") (class "Default")
      (node (ref "C1") (pin "2") (pinfunction "2_2") (pintype "passive"))
      (node (ref "R1") (pin "2") (pinfunction "2_2") (pintype "passive"))
    )
    (net (code "20") (name "Net-(C2-Pad2)") (class "Default")
      (node (ref "C2") (pin "2") (pinfunction "2_2") (pintype "passive"))
      (node (ref "R2") (pin "2") (pinfunction "2_2") (pintype "passive"))
    )
    (net (code "21") (name "Net-(C3-Pad2)") (class "Default")
      (node (ref "C3") (pin "2") (pinfunction "2_2") (pintype "passive"))
      (node (ref "R3") (pin "2") (pinfunction "2_2") (pintype "passive"))
    )
    (net (code "22") (name "Net-(C4-Pad2)") (class "Default")
      (node (ref "C4") (pin "2") (pinfunction "2_2") (pintype "passive"))
      (node (ref "R4") (pin "2") (pinfunction "2_2") (pintype "passive"))
    )
    (net (code "23") (name "Net-(C5-Pad1)") (class "Default")
      (node (ref "C5") (pin "1") (pinfunction "1_1") (pintype "passive"))
      (node (ref "R1") (pin "1") (pinfunction "1_1") (pintype "passive"))
      (node (ref "R2") (pin "1") (pinfunction "1_1") (pintype "passive"))
      (node (ref "R3") (pin "1") (pinfunction "1_1") (pintype "passive"))
      (node (ref "R4") (pin "1") (pinfunction "1_1") (pintype "passive"))
    )
    (net (code "24") (name "Net-(D2-PadA)") (class "Default")
      (node (ref "D2") (pin "A") (pinfunction "A_A") (pintype "passive"))
      (node (ref "R13") (pin "2") (pinfunction "2_2") (pintype "passive"))
    )
    (net (code "25") (name "Net-(D3-PadA)") (class "Default")
      (node (ref "D3") (pin "A") (pinfunction "A_A") (pintype "passive"))
      (node (ref "R14") (pin "2") (pinfunction "2_2") (pintype "passive"))
    )
    (net (code "26") (name "Net-(D4-PadA)") (class "Default")
      (node (ref "D4") (pin "A") (pinfunction "A_A") (pintype "passive"))
      (node (ref "R16") (pin "2") (pinfunction "2_2") (pintype "passive"))
    )
    (net (code "27") (name "Net-(D7-PadA)") (class "Default")
      (node (ref "D7") (pin "A") (pinfunction "A_A") (pintype "passive"))
      (node (ref "R18") (pin "2") (pinfunction "2_2") (pintype "passive"))
    )
    (net (code "28") (name "Net-(D8-PadA)") (class "Default")
      (node (ref "D8") (pin "A") (pinfunction "A_A") (pintype "passive"))
      (node (ref "R19") (pin "2") (pinfunction "2_2") (pintype "passive"))
    )
    (net (code "29") (name "Net-(D10-PadA)") (class "Default")
      (node (ref "D10") (pin "A") (pinfunction "A_A") (pintype "passive"))
      (node (ref "R26") (pin "1") (pinfunction "1_1") (pintype "passive"))
    )
    (net (code "30") (name "Net-(D11-PadA)") (class "Default")
      (node (ref "D11") (pin "A") (pinfunction "A_A") (pintype "passive"))
      (node (ref "R27") (pin "1") (pinfunction "1_1") (pintype "passive"))
    )
    (net (code "31") (name "Net-(D12-PadA)") (class "Default")
      (node (ref "D12") (pin "A") (pinfunction "A_A") (pintype "passive"))
      (node (ref "R22") (pin "1") (pinfunction "1_1") (pintype "passive"))
    )
    (net (code "32") (name "Net-(D13-PadA)") (class "Default")
      (node (ref "D13") (pin "A") (pinfunction "A_A") (pintype "passive"))
      (node (ref "R23") (pin "1") (pinfunction "1_1") (pintype "passive"))
    )
    (net (code "33") (name "Net-(R5-Pad1)") (class "Default")
      (node (ref "R5") (pin "1") (pinfunction "1_1") (pintype "passive"))
      (node (ref "T1") (pin "3") (pinfunction "3_3") (pintype "passive"))
    )
    (net (code "34") (name "Net-(R6-Pad1)") (class "Default")
      (node (ref "R6") (pin "1") (pinfunction "1_1") (pintype "passive"))
      (node (ref "T1") (pin "1") (pinfunction "1_1") (pintype "passive"))
    )
    (net (code "35") (name "Net-(R7-Pad1)") (class "Default")
      (node (ref "R7") (pin "1") (pinfunction "1_1") (pintype "passive"))
      (node (ref "T1") (pin "8") (pinfunction "8_8") (pintype "passive"))
    )
    (net (code "36") (name "Net-(R8-Pad1)") (class "Default")
      (node (ref "R8") (pin "1") (pinfunction "1_1") (pintype "passive"))
      (node (ref "T1") (pin "6") (pinfunction "6_6") (pintype "passive"))
    )
    (net (code "37") (name "Net-(U1-CLS)") (class "Default")
      (node (ref "R10") (pin "2") (pinfunction "2_2") (pintype "passive"))
      (node (ref "U1") (pin "3") (pinfunction "CLS_3") (pintype "output"))
    )
    (net (code "38") (name "Net-(U1-DEN)") (class "Default")
      (node (ref "R9") (pin "1") (pinfunction "1_1") (pintype "passive"))
      (node (ref "U1") (pin "2") (pinfunction "DEN_2") (pintype "bidirectional"))
    )
    (net (code "39") (name "Net-(U2-ANODE)") (class "Default")
      (node (ref "R15") (pin "2") (pinfunction "2_2") (pintype "passive"))
      (node (ref "U2") (pin "1") (pinfunction "ANODE_1") (pintype "passive"))
    )
    (net (code "40") (name "Net-(U3-RBIAS)") (class "Default")
      (node (ref "R30") (pin "1") (pinfunction "1_1") (pintype "passive"))
      (node (ref "U3") (pin "53") (pinfunction "RBIAS_53") (pintype "passive"))
    )
    (net (code "41") (name "Net-(U3-RC6{slash}TX1{slash}CK1)") (class "Default")
      (node (ref "R24") (pin "2") (pinfunction "2_2") (pintype "passive"))
      (node (ref "U3") (pin "31") (pinfunction "RC6/TX1/CK1_31") (pintype "passive"))
    )
    (net (code "42") (name "Net-(U3-RC7{slash}RX1{slash}DT1)") (class "Default")
      (node (ref "R25") (pin "2") (pinfunction "2_2") (pintype "passive"))
      (node (ref "U3") (pin "32") (pinfunction "RC7/RX1/DT1_32") (pintype "passive"))
    )
    (net (code "43") (name "Net-(U3-TPOUT+)") (class "Default")
      (node (ref "C24") (pin "2") (pinfunction "2_2") (pintype "passive"))
      (node (ref "L4") (pin "1") (pinfunction "1_1") (pintype "passive"))
      (node (ref "U3") (pin "51") (pinfunction "TPOUT+_51") (pintype "passive"))
    )
    (net (code "44") (name "Net-(U3-TPOUT-)") (class "Default")
      (node (ref "C25") (pin "2") (pinfunction "2_2") (pintype "passive"))
      (node (ref "L5") (pin "1") (pinfunction "1_1") (pintype "passive"))
      (node (ref "U3") (pin "50") (pinfunction "TPOUT-_50") (pintype "passive"))
    )
    (net (code "45") (name "Net-(U3-VDDCORE{slash}VCAP)") (class "Default")
      (node (ref "C26") (pin "1") (pinfunction "1_1") (pintype "passive"))
      (node (ref "U3") (pin "10") (pinfunction "VDDCORE/VCAP_10") (pintype "passive"))
    )
    (net (code "46") (name "Net-(U5A-O)") (class "Default")
      (node (ref "R29") (pin "1") (pinfunction "1_1") (pintype "passive"))
      (node (ref "U5") (pin "4") (pinfunction "O_4") (pintype "tri_state"))
    )
    (net (code "47") (name "PGC") (class "Default")
      (node (ref "J3") (pin "5") (pinfunction "ICSP_CLK/PGC_5") (pintype "output"))
      (node (ref "U3") (pin "42") (pinfunction "RB6/KBI2/PGC_42") (pintype "passive"))
    )
    (net (code "48") (name "PGD") (class "Default")
      (node (ref "J3") (pin "4") (pinfunction "ICSP_DAT/PGD_4") (pintype "bidirectional"))
      (node (ref "U3") (pin "37") (pinfunction "RB7/KBI3/PGD_37") (pintype "passive"))
    )
    (net (code "49") (name "RD_CT") (class "Default")
      (node (ref "C32") (pin "1") (pinfunction "1_1") (pintype "passive"))
      (node (ref "R33") (pin "1") (pinfunction "1_1") (pintype "passive"))
      (node (ref "R34") (pin "1") (pinfunction "1_1") (pintype "passive"))
      (node (ref "T1") (pin "7") (pinfunction "7_7") (pintype "passive"))
    )
    (net (code "50") (name "RD_N") (class "Default")
      (node (ref "D6") (pin "2") (pinfunction "I/O1_2") (pintype "bidirectional"))
      (node (ref "R34") (pin "2") (pinfunction "2_2") (pintype "passive"))
      (node (ref "R7") (pin "2") (pinfunction "2_2") (pintype "passive"))
      (node (ref "U3") (pin "46") (pinfunction "TPIN-_46") (pintype "passive"))
    )
    (net (code "51") (name "RD_P") (class "Default")
      (node (ref "D6") (pin "3") (pinfunction "I/O2_3") (pintype "bidirectional"))
      (node (ref "R33") (pin "2") (pinfunction "2_2") (pintype "passive"))
      (node (ref "R8") (pin "2") (pinfunction "2_2") (pintype "passive"))
      (node (ref "U3") (pin "47") (pinfunction "TPIN+_47") (pintype "passive"))
    )
    (net (code "52") (name "RTN") (class "Default")
      (node (ref "C9") (pin "-") (pinfunction "-_-") (pintype "passive"))
      (node (ref "D3") (pin "C") (pinfunction "C_C") (pintype "passive"))
      (node (ref "PS1") (pin "2") (pinfunction "GND_2") (pintype "power_in"))
      (node (ref "R12") (pin "2") (pinfunction "2_2") (pintype "passive"))
      (node (ref "TP3") (pin "1") (pinfunction "P$1_1") (pintype "bidirectional"))
      (node (ref "U1") (pin "5") (pinfunction "RTN_5") (pintype "passive"))
      (node (ref "U1") (pin "8") (pinfunction "APD_8") (pintype "input"))
    )
    (net (code "53") (name "RXIN") (class "Default")
      (node (ref "J4") (pin "2") (pinfunction "1_2") (pintype "passive"))
      (node (ref "R25") (pin "1") (pinfunction "1_1") (pintype "passive"))
    )
    (net (code "54") (name "RX_CT") (class "Default")
      (node (ref "BR1") (pin "AC2") (pinfunction "AC2_AC2") (pintype "passive"))
      (node (ref "C4") (pin "1") (pinfunction "1_1") (pintype "passive"))
      (node (ref "T1") (pin "10") (pinfunction "10_10") (pintype "passive"))
      (node (ref "TP6") (pin "1") (pinfunction "P$1_1") (pintype "bidirectional"))
    )
    (net (code "55") (name "RX_N") (class "Default")
      (node (ref "J1") (pin "6") (pinfunction "6_6") (pintype "passive"))
      (node (ref "T1") (pin "9") (pinfunction "9_9") (pintype "passive"))
    )
    (net (code "56") (name "RX_P") (class "Default")
      (node (ref "J1") (pin "3") (pinfunction "3_3") (pintype "passive"))
      (node (ref "T1") (pin "11") (pinfunction "11_11") (pintype "passive"))
    )
    (net (code "57") (name "SCK") (class "Default")
      (node (ref "U3") (pin "34") (pinfunction "RC3/SCK1/SCL1_34") (pintype "passive"))
      (node (ref "U4") (pin "1") (pinfunction "SCK_1") (pintype "input"))
    )
    (net (code "58") (name "SPARE_0") (class "Default")
      (node (ref "BR2") (pin "AC1") (pinfunction "AC1_AC1") (pintype "passive"))
      (node (ref "C2") (pin "1") (pinfunction "1_1") (pintype "passive"))
      (node (ref "J1") (pin "4") (pinfunction "4_4") (pintype "passive"))
      (node (ref "J1") (pin "5") (pinfunction "5_5") (pintype "passive"))
      (node (ref "TP5") (pin "1") (pinfunction "P$1_1") (pintype "bidirectional"))
    )
    (net (code "59") (name "SPARE_1") (class "Default")
      (node (ref "BR2") (pin "AC2") (pinfunction "AC2_AC2") (pintype "passive"))
      (node (ref "C1") (pin "1") (pinfunction "1_1") (pintype "passive"))
      (node (ref "J1") (pin "7") (pinfunction "7_7") (pintype "passive"))
      (node (ref "J1") (pin "8") (pinfunction "8_8") (pintype "passive"))
      (node (ref "TP4") (pin "1") (pinfunction "P$1_1") (pintype "bidirectional"))
    )
    (net (code "60") (name "SW1") (class "Default")
      (node (ref "R20") (pin "1") (pinfunction "1_1") (pintype "passive"))
      (node (ref "SW1") (pin "1") (pinfunction "S_1") (pintype "passive"))
      (node (ref "SW1") (pin "2") (pinfunction "S1_2") (pintype "passive"))
      (node (ref "U3") (pin "3") (pinfunction "RB0/INT0/FLT0_3") (pintype "passive"))
    )
    (net (code "61") (name "SW2") (class "Default")
      (node (ref "R21") (pin "1") (pinfunction "1_1") (pintype "passive"))
      (node (ref "SW2") (pin "1") (pinfunction "S_1") (pintype "passive"))
      (node (ref "SW2") (pin "2") (pinfunction "S1_2") (pintype "passive"))
      (node (ref "U3") (pin "4") (pinfunction "RB1/INT1_4") (pintype "passive"))
    )
    (net (code "62") (name "T2P") (class "Default")
      (node (ref "D4") (pin "C") (pinfunction "C_C") (pintype "passive"))
      (node (ref "TP11") (pin "1") (pinfunction "P$1_1") (pintype "bidirectional"))
      (node (ref "U1") (pin "7") (pinfunction "T2P_7") (pintype "output"))
      (node (ref "U2") (pin "2") (pinfunction "CATHODE_2") (pintype "passive"))
    )
    (net (code "63") (name "TD_CT") (class "Default")
      (node (ref "C16") (pin "1") (pinfunction "1_1") (pintype "passive"))
      (node (ref "C17") (pin "1") (pinfunction "1_1") (pintype "passive"))
      (node (ref "C18") (pin "1") (pinfunction "1_1") (pintype "passive"))
      (node (ref "C19") (pin "1") (pinfunction "1_1") (pintype "passive"))
      (node (ref "C20") (pin "1") (pinfunction "1_1") (pintype "passive"))
      (node (ref "C21") (pin "1") (pinfunction "1_1") (pintype "passive"))
      (node (ref "C22") (pin "1") (pinfunction "1_1") (pintype "passive"))
      (node (ref "C23") (pin "1") (pinfunction "1_1") (pintype "passive"))
      (node (ref "C31") (pin "1") (pinfunction "1_1") (pintype "passive"))
      (node (ref "L3") (pin "1") (pinfunction "1_1") (pintype "passive"))
      (node (ref "R31") (pin "2") (pinfunction "2_2") (pintype "passive"))
      (node (ref "R32") (pin "2") (pinfunction "2_2") (pintype "passive"))
      (node (ref "T1") (pin "2") (pinfunction "2_2") (pintype "passive"))
      (node (ref "U3") (pin "48") (pinfunction "VDDRX_48") (pintype "passive"))
      (node (ref "U3") (pin "49") (pinfunction "VDDTX_49") (pintype "passive"))
      (node (ref "U3") (pin "54") (pinfunction "VDDPLL_54") (pintype "passive"))
    )
    (net (code "64") (name "TD_N") (class "Default")
      (node (ref "D5") (pin "2") (pinfunction "I/O1_2") (pintype "bidirectional"))
      (node (ref "L5") (pin "2") (pinfunction "2_2") (pintype "passive"))
      (node (ref "R32") (pin "1") (pinfunction "1_1") (pintype "passive"))
      (node (ref "R5") (pin "2") (pinfunction "2_2") (pintype "passive"))
    )
    (net (code "65") (name "TD_P") (class "Default")
      (node (ref "D5") (pin "3") (pinfunction "I/O2_3") (pintype "bidirectional"))
      (node (ref "L4") (pin "2") (pinfunction "2_2") (pintype "passive"))
      (node (ref "R31") (pin "1") (pinfunction "1_1") (pintype "passive"))
      (node (ref "R6") (pin "2") (pinfunction "2_2") (pintype "passive"))
    )
    (net (code "66") (name "TXOUT") (class "Default")
      (node (ref "J4") (pin "1") (pinfunction "1_1") (pintype "passive"))
      (node (ref "R24") (pin "1") (pinfunction "1_1") (pintype "passive"))
    )
    (net (code "67") (name "TX_CT") (class "Default")
      (node (ref "BR1") (pin "AC1") (pinfunction "AC1_AC1") (pintype "passive"))
      (node (ref "C3") (pin "1") (pinfunction "1_1") (pintype "passive"))
      (node (ref "T1") (pin "15") (pinfunction "15_15") (pintype "passive"))
      (node (ref "TP7") (pin "1") (pinfunction "P$1_1") (pintype "bidirectional"))
    )
    (net (code "68") (name "TX_N") (class "Default")
      (node (ref "J1") (pin "2") (pinfunction "2_2") (pintype "passive"))
      (node (ref "T1") (pin "14") (pinfunction "14_14") (pintype "passive"))
    )
    (net (code "69") (name "TX_P") (class "Default")
      (node (ref "J1") (pin "1") (pinfunction "1_1") (pintype "passive"))
      (node (ref "T1") (pin "16") (pinfunction "16_16") (pintype "passive"))
    )
    (net (code "70") (name "VNNIN") (class "Default")
      (node (ref "C8") (pin "2") (pinfunction "2_2") (pintype "passive"))
      (node (ref "D1") (pin "A") (pinfunction "A_A") (pintype "passive"))
      (node (ref "D2") (pin "C") (pinfunction "C_C") (pintype "passive"))
      (node (ref "L2") (pin "2") (pinfunction "2_2") (pintype "passive"))
      (node (ref "R10") (pin "1") (pinfunction "1_1") (pintype "passive"))
      (node (ref "TP2") (pin "1") (pinfunction "P$1_1") (pintype "bidirectional"))
      (node (ref "U1") (pin "4") (pinfunction "VSS_4") (pintype "power_in"))
      (node (ref "U1") (pin "EPAD") (pinfunction "EPAD_EPAD") (pintype "passive"))
    )
    (net (code "71") (name "VPPIN") (class "Default")
      (node (ref "C8") (pin "1") (pinfunction "1_1") (pintype "passive"))
      (node (ref "C9") (pin "+") (pinfunction "+_+") (pintype "passive"))
      (node (ref "D1") (pin "C") (pinfunction "C_C") (pintype "passive"))
      (node (ref "L1") (pin "2") (pinfunction "2_2") (pintype "passive"))
      (node (ref "PS1") (pin "3") (pinfunction "VIN_3") (pintype "input"))
      (node (ref "R11") (pin "1") (pinfunction "1_1") (pintype "passive"))
      (node (ref "R13") (pin "1") (pinfunction "1_1") (pintype "passive"))
      (node (ref "R14") (pin "1") (pinfunction "1_1") (pintype "passive"))
      (node (ref "R15") (pin "1") (pinfunction "1_1") (pintype "passive"))
      (node (ref "R16") (pin "1") (pinfunction "1_1") (pintype "passive"))
      (node (ref "R9") (pin "2") (pinfunction "2_2") (pintype "passive"))
      (node (ref "TP1") (pin "1") (pinfunction "P$1_1") (pintype "bidirectional"))
      (node (ref "U1") (pin "1") (pinfunction "VDD_1") (pintype "input"))
    )
    (net (code "72") (name "unconnected-(J3-LVP-Pad6)") (class "Default")
      (node (ref "J3") (pin "6") (pinfunction "LVP_6") (pintype "bidirectional"))
    )
    (net (code "73") (name "unconnected-(OSC1-NC-Pad2)") (class "Default")
      (node (ref "OSC1") (pin "2") (pinfunction "NC_2") (pintype "bidirectional"))
    )
    (net (code "74") (name "unconnected-(PS1-TRIM-Pad5)") (class "Default")
      (node (ref "PS1") (pin "5") (pinfunction "TRIM_5") (pintype "passive"))
    )
    (net (code "75") (name "unconnected-(T1-Pad4)") (class "Default")
      (node (ref "T1") (pin "4") (pinfunction "4_4") (pintype "passive"))
    )
    (net (code "76") (name "unconnected-(T1-Pad5)") (class "Default")
      (node (ref "T1") (pin "5") (pinfunction "5_5") (pintype "passive"))
    )
    (net (code "77") (name "unconnected-(T1-Pad12)") (class "Default")
      (node (ref "T1") (pin "12") (pinfunction "12_12") (pintype "passive"))
    )
    (net (code "78") (name "unconnected-(T1-Pad13)") (class "Default")
      (node (ref "T1") (pin "13") (pinfunction "13_13") (pintype "passive"))
    )
    (net (code "79") (name "unconnected-(U3-OSC2{slash}CLKO-Pad40)") (class "Default")
      (node (ref "U3") (pin "40") (pinfunction "OSC2/CLKO_40") (pintype "passive"))
    )
    (net (code "80") (name "unconnected-(U3-RA2{slash}AN2{slash}VREF--Pad22)") (class "Default")
      (node (ref "U3") (pin "22") (pinfunction "RA2/AN2/VREF-_22") (pintype "passive"))
    )
    (net (code "81") (name "unconnected-(U3-RA3{slash}AN3{slash}VREF+-Pad21)") (class "Default")
      (node (ref "U3") (pin "21") (pinfunction "RA3/AN3/VREF+_21") (pintype "passive"))
    )
    (net (code "82") (name "unconnected-(U3-RA4{slash}T0CKI-Pad28)") (class "Default")
      (node (ref "U3") (pin "28") (pinfunction "RA4/T0CKI_28") (pintype "passive"))
    )
    (net (code "83") (name "unconnected-(U3-RA5{slash}AN4-Pad27)") (class "Default")
      (node (ref "U3") (pin "27") (pinfunction "RA5/AN4_27") (pintype "passive"))
    )
    (net (code "84") (name "unconnected-(U3-RB3{slash}INT3-Pad6)") (class "Default")
      (node (ref "U3") (pin "6") (pinfunction "RB3/INT3_6") (pintype "passive"))
    )
    (net (code "85") (name "unconnected-(U3-RB5{slash}KBI1-Pad43)") (class "Default")
      (node (ref "U3") (pin "43") (pinfunction "RB5/KBI1_43") (pintype "passive"))
    )
    (net (code "86") (name "unconnected-(U3-RC0{slash}T1OSO{slash}T13CKI-Pad30)") (class "Default")
      (node (ref "U3") (pin "30") (pinfunction "RC0/T1OSO/T13CKI_30") (pintype "passive"))
    )
    (net (code "87") (name "unconnected-(U3-RC1{slash}T1OSI{slash}ECCP2{slash}P2A-Pad29)") (class "Default")
      (node (ref "U3") (pin "29") (pinfunction "RC1/T1OSI/ECCP2/P2A_29") (pintype "passive"))
    )
    (net (code "88") (name "unconnected-(U3-RC2{slash}ECCP1{slash}P1A-Pad33)") (class "Default")
      (node (ref "U3") (pin "33") (pinfunction "RC2/ECCP1/P1A_33") (pintype "passive"))
    )
    (net (code "89") (name "unconnected-(U3-RD0{slash}P1B-Pad60)") (class "Default")
      (node (ref "U3") (pin "60") (pinfunction "RD0/P1B_60") (pintype "passive"))
    )
    (net (code "90") (name "unconnected-(U3-RD1{slash}ECCP3{slash}P3A-Pad59)") (class "Default")
      (node (ref "U3") (pin "59") (pinfunction "RD1/ECCP3/P3A_59") (pintype "passive"))
    )
    (net (code "91") (name "unconnected-(U3-RD2{slash}CCP4{slash}P3D-Pad58)") (class "Default")
      (node (ref "U3") (pin "58") (pinfunction "RD2/CCP4/P3D_58") (pintype "passive"))
    )
    (net (code "92") (name "unconnected-(U3-RE0{slash}P2D-Pad2)") (class "Default")
      (node (ref "U3") (pin "2") (pinfunction "RE0/P2D_2") (pintype "passive"))
    )
    (net (code "93") (name "unconnected-(U3-RE1{slash}P2C-Pad1)") (class "Default")
      (node (ref "U3") (pin "1") (pinfunction "RE1/P2C_1") (pintype "passive"))
    )
    (net (code "94") (name "unconnected-(U3-RE3{slash}P3C-Pad63)") (class "Default")
      (node (ref "U3") (pin "63") (pinfunction "RE3/P3C_63") (pintype "passive"))
    )
    (net (code "95") (name "unconnected-(U3-RF1{slash}AN6{slash}C2OUT-Pad17)") (class "Default")
      (node (ref "U3") (pin "17") (pinfunction "RF1/AN6/C2OUT_17") (pintype "passive"))
    )
    (net (code "96") (name "unconnected-(U3-RF2{slash}AN7{slash}C1OUT-Pad16)") (class "Default")
      (node (ref "U3") (pin "16") (pinfunction "RF2/AN7/C1OUT_16") (pintype "passive"))
    )
    (net (code "97") (name "unconnected-(U3-RF3{slash}AN8-Pad15)") (class "Default")
      (node (ref "U3") (pin "15") (pinfunction "RF3/AN8_15") (pintype "passive"))
    )
    (net (code "98") (name "unconnected-(U3-RF4{slash}AN9-Pad14)") (class "Default")
      (node (ref "U3") (pin "14") (pinfunction "RF4/AN9_14") (pintype "passive"))
    )
    (net (code "99") (name "unconnected-(U3-RF5{slash}AN10{slash}CVREF-Pad13)") (class "Default")
      (node (ref "U3") (pin "13") (pinfunction "RF5/AN10/CVREF_13") (pintype "passive"))
    )
    (net (code "100") (name "unconnected-(U3-RF6{slash}AN11-Pad12)") (class "Default")
      (node (ref "U3") (pin "12") (pinfunction "RF6/AN11_12") (pintype "passive"))
    )
    (net (code "101") (name "unconnected-(U3-RF7{slash}~{SS1}-Pad11)") (class "Default")
      (node (ref "U3") (pin "11") (pinfunction "RF7/~{SS1}_11") (pintype "passive"))
    )
    (net (code "102") (name "unconnected-(U3-RG4{slash}CCP5{slash}P1D-Pad8)") (class "Default")
      (node (ref "U3") (pin "8") (pinfunction "RG4/CCP5/P1D_8") (pintype "passive"))
    )
    (net (code "103") (name "{slash}MCLR") (class "Default")
      (node (ref "J3") (pin "1") (pinfunction "VPP/MCLR_1") (pintype "passive"))
      (node (ref "R28") (pin "2") (pinfunction "2_2") (pintype "passive"))
      (node (ref "U3") (pin "7") (pinfunction "~{MCLR}_7") (pintype "passive"))
    )
  )
)
